# uController_Untilities.net
KiCad netlist of a schematic drawn in Altium Designer
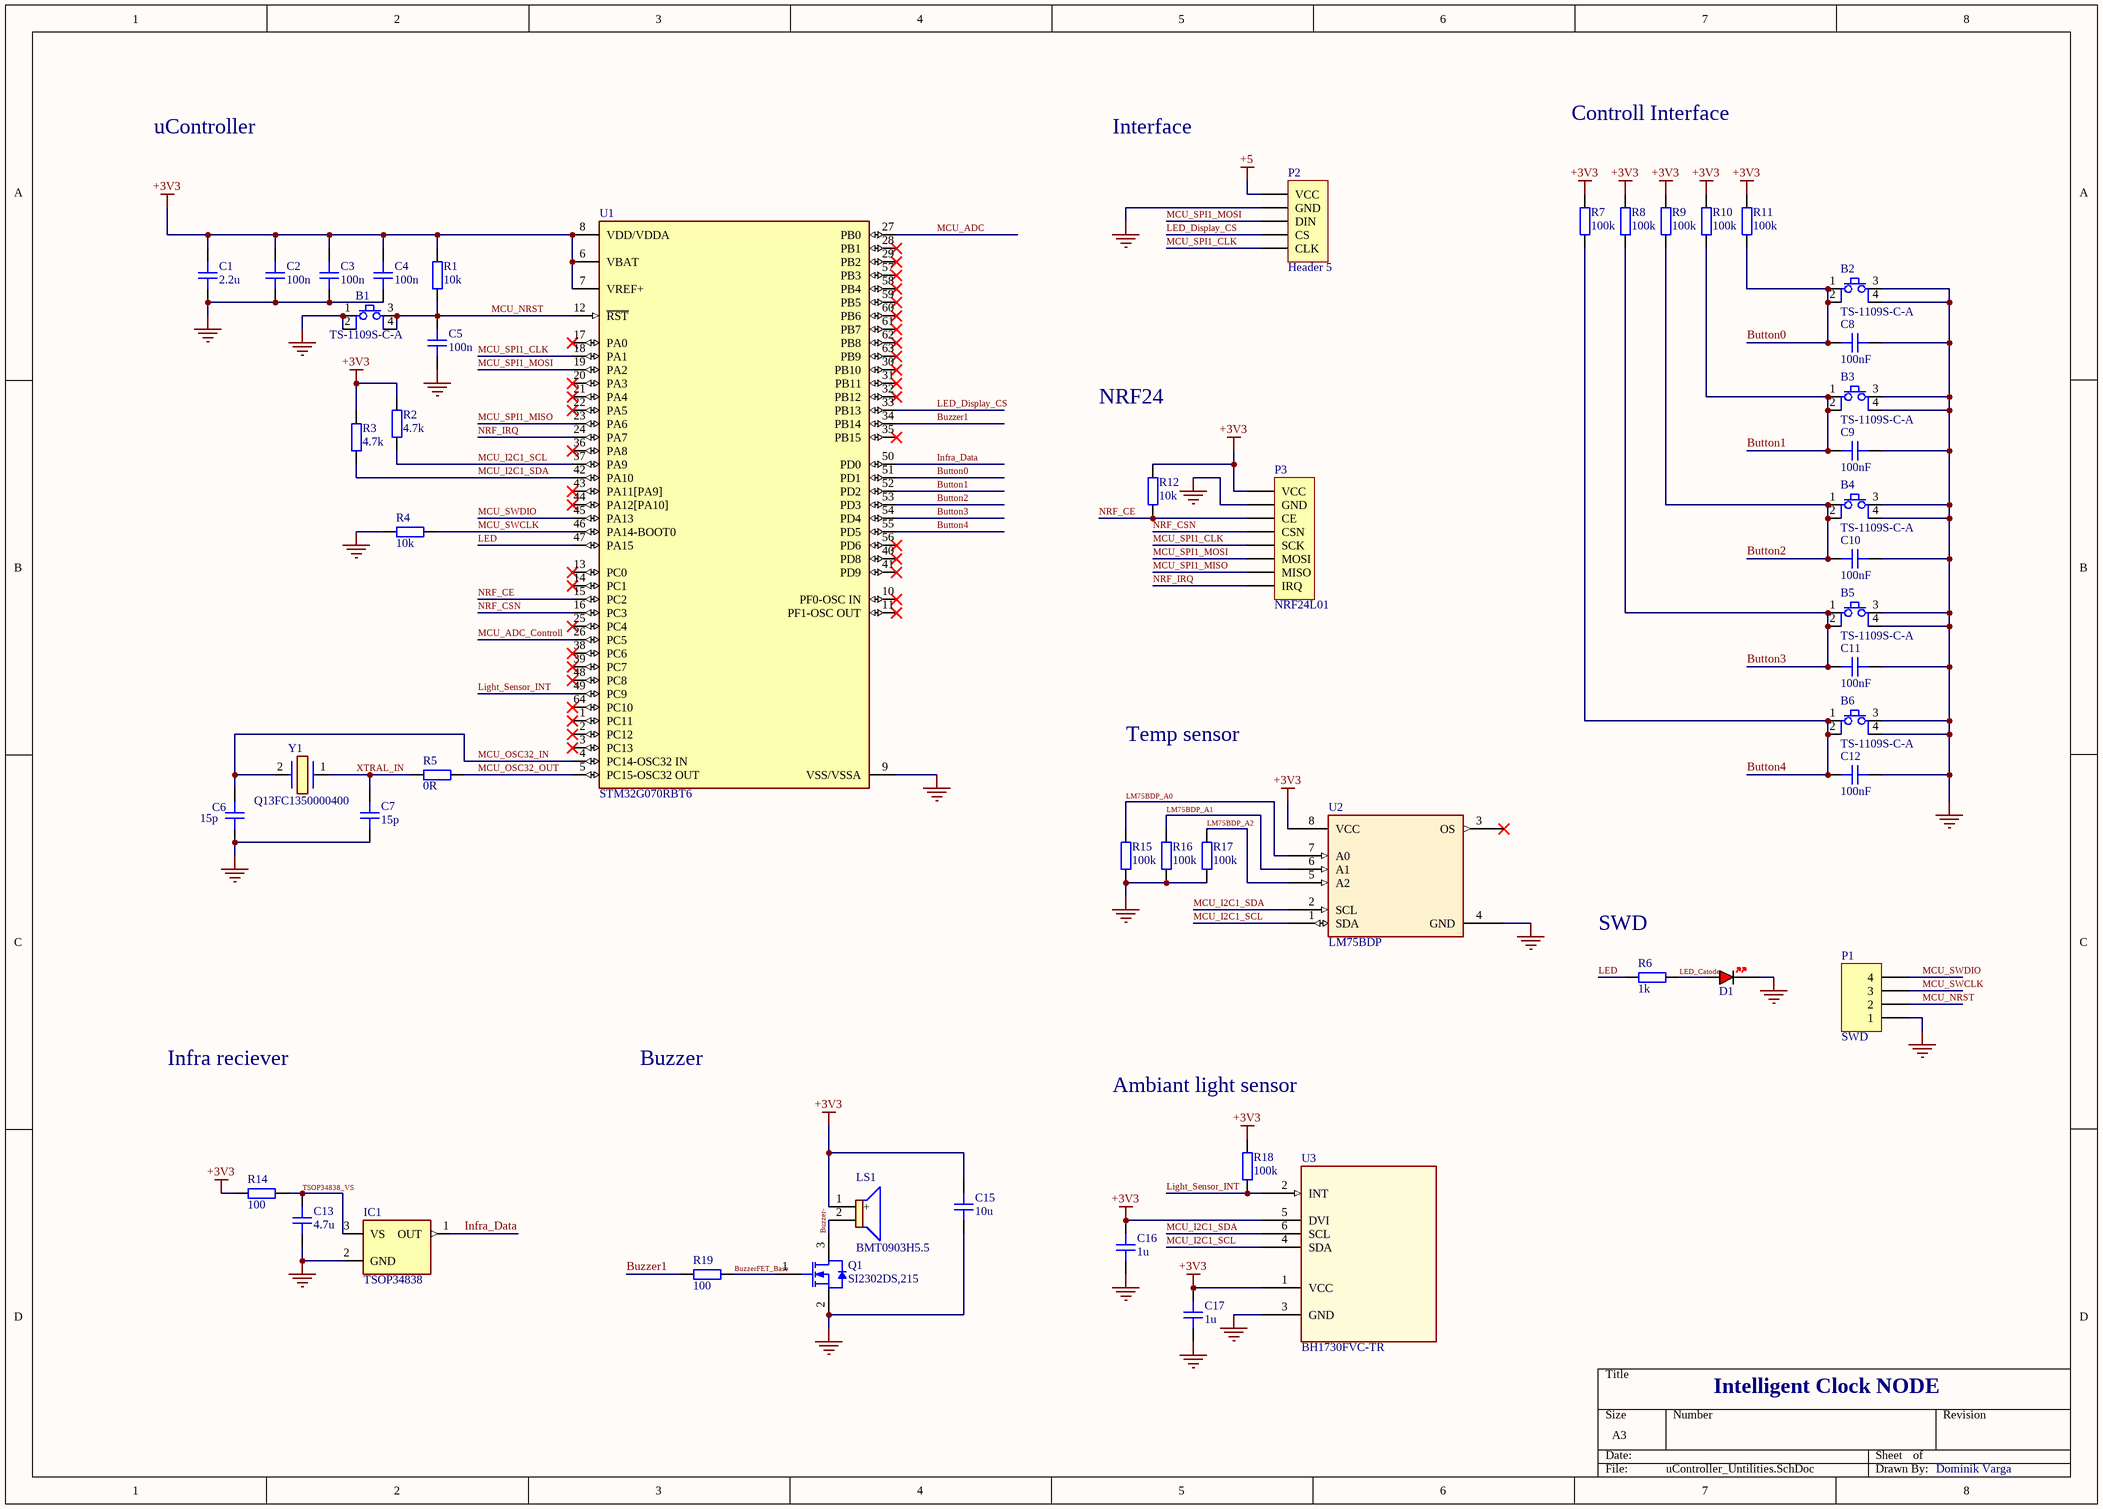
[diagram p0: uController_Untilities.SchDoc]

(export (version "E")
  (design (tool "Eeschema 10.0.6"))
  (components
    (comp (ref "B1")
      (value "TS-1109S-C-A")
      (footprint "SMD_Button")
      (description "Basic SMD button")
      (fields (field (name "MANUFACTURER") "XKB Connectivity"))
      (libsource (lib "OnlabComponents") (part "TS-1109S-C-A"))
    )
    (comp (ref "B2")
      (value "TS-1109S-C-A")
      (footprint "SMD_Button")
      (description "Basic SMD button")
      (fields (field (name "MANUFACTURER") "XKB Connectivity"))
      (libsource (lib "OnlabComponents") (part "TS-1109S-C-A"))
    )
    (comp (ref "B3")
      (value "TS-1109S-C-A")
      (footprint "SMD_Button")
      (description "Basic SMD button")
      (fields (field (name "MANUFACTURER") "XKB Connectivity"))
      (libsource (lib "OnlabComponents") (part "TS-1109S-C-A"))
    )
    (comp (ref "B4")
      (value "TS-1109S-C-A")
      (footprint "SMD_Button")
      (description "Basic SMD button")
      (fields (field (name "MANUFACTURER") "XKB Connectivity"))
      (libsource (lib "OnlabComponents") (part "TS-1109S-C-A"))
    )
    (comp (ref "B5")
      (value "TS-1109S-C-A")
      (footprint "SMD_Button")
      (description "Basic SMD button")
      (fields (field (name "MANUFACTURER") "XKB Connectivity"))
      (libsource (lib "OnlabComponents") (part "TS-1109S-C-A"))
    )
    (comp (ref "B6")
      (value "TS-1109S-C-A")
      (footprint "SMD_Button")
      (description "Basic SMD button")
      (fields (field (name "MANUFACTURER") "XKB Connectivity"))
      (libsource (lib "OnlabComponents") (part "TS-1109S-C-A"))
    )
    (comp (ref "C1")
      (value "2.2u")
      (footprint "CAP_0603")
      (description "Capacitor SMD 0603 10V")
      (libsource (lib "Schematic-Lib-PhilsLab") (part "CAP_0603_10V"))
    )
    (comp (ref "C2")
      (value "100n")
      (footprint "CAP_0603")
      (description "Capacitor SMD 0603 10V")
      (libsource (lib "Schematic-Lib-PhilsLab") (part "CAP_0603_10V"))
    )
    (comp (ref "C3")
      (value "100n")
      (footprint "CAP_0603")
      (description "Capacitor SMD 0603 10V")
      (libsource (lib "Schematic-Lib-PhilsLab") (part "CAP_0603_10V"))
    )
    (comp (ref "C4")
      (value "100n")
      (footprint "CAP_0603")
      (description "Capacitor SMD 0603 10V")
      (libsource (lib "Schematic-Lib-PhilsLab") (part "CAP_0603_10V"))
    )
    (comp (ref "C5")
      (value "100n")
      (footprint "CAP_0603")
      (description "Capacitor SMD 0603 10V")
      (libsource (lib "Schematic-Lib-PhilsLab") (part "CAP_0603_10V"))
    )
    (comp (ref "C6")
      (value "15p")
      (footprint "CAP_0603")
      (description "Capacitor SMD 0603 10V")
      (libsource (lib "Schematic-Lib-PhilsLab") (part "CAP_0603_10V"))
    )
    (comp (ref "C7")
      (value "15p")
      (footprint "CAP_0603")
      (description "Capacitor SMD 0603 10V")
      (libsource (lib "Schematic-Lib-PhilsLab") (part "CAP_0603_10V"))
    )
    (comp (ref "C8")
      (value "100nF")
      (footprint "CAP_0603")
      (description "Capacitor SMD 0603 10V")
      (libsource (lib "Schematic-Lib-PhilsLab") (part "CAP_0603_10V"))
    )
    (comp (ref "C9")
      (value "100nF")
      (footprint "CAP_0603")
      (description "Capacitor SMD 0603 10V")
      (libsource (lib "Schematic-Lib-PhilsLab") (part "CAP_0603_10V"))
    )
    (comp (ref "C10")
      (value "100nF")
      (footprint "CAP_0603")
      (description "Capacitor SMD 0603 10V")
      (libsource (lib "Schematic-Lib-PhilsLab") (part "CAP_0603_10V"))
    )
    (comp (ref "C11")
      (value "100nF")
      (footprint "CAP_0603")
      (description "Capacitor SMD 0603 10V")
      (libsource (lib "Schematic-Lib-PhilsLab") (part "CAP_0603_10V"))
    )
    (comp (ref "C12")
      (value "100nF")
      (footprint "CAP_0603")
      (description "Capacitor SMD 0603 10V")
      (libsource (lib "Schematic-Lib-PhilsLab") (part "CAP_0603_10V"))
    )
    (comp (ref "C13")
      (value "4.7u")
      (footprint "CAP_0603")
      (description "Capacitor SMD 0603 10V")
      (libsource (lib "Schematic-Lib-PhilsLab") (part "CAP_0603_10V"))
    )
    (comp (ref "C15")
      (value "10u")
      (footprint "CAP_0603")
      (description "Capacitor SMD 0603 10V")
      (libsource (lib "Schematic-Lib-PhilsLab") (part "CAP_0603_10V"))
    )
    (comp (ref "C16")
      (value "1u")
      (footprint "CAP_0603")
      (description "Capacitor SMD 0603 10V")
      (libsource (lib "Schematic-Lib-PhilsLab") (part "CAP_0603_10V"))
    )
    (comp (ref "C17")
      (value "1u")
      (footprint "CAP_0603")
      (description "Capacitor SMD 0603 10V")
      (libsource (lib "Schematic-Lib-PhilsLab") (part "CAP_0603_10V"))
    )
    (comp (ref "D1")
      (value "RED")
      (footprint "LED_0603_RED")
      (description "LED 0603 RED SMD")
      (libsource (lib "Schematic-Lib-PhilsLab") (part "LED_0603_RED"))
    )
    (comp (ref "IC1")
      (value "TSOP34838")
      (footprint "TSOP4856")
      (description "Integrated Circuit")
      (fields (field (name "MOUSER PART NUMBER") "782-TSOP34838"))
      (libsource (lib "OnlabComponents") (part "TSOP34838"))
    )
    (comp (ref "LS1")
      (value "BMT0903H5.5")
      (footprint "BMT0903H5.5")
      (description "Loudspeaker or Buzzer")
      (fields (field (name "MANUFACTURER") "BESTAR,LOUDITY"))
      (libsource (lib "OnlabComponents") (part "BMT0903H5.5"))
    )
    (comp (ref "P1")
      (value "SWD")
      (footprint "HDR1X4")
      (description "Header, 4-Pin")
      (fields (field (name "PUBLISHER") "Altium Limited"))
      (libsource (lib "Miscellaneous Connectors") (part "Header 4"))
    )
    (comp (ref "P2")
      (value "Header 5")
      (footprint "HDR1X5")
      (description "Header, 5-Pin")
      (fields (field (name "PUBLISHER") "Altium Limited"))
      (libsource (lib "Miscellaneous Connectors") (part "Header 5"))
    )
    (comp (ref "P3")
      (value "NRF24L01")
      (footprint "MHDR1X8")
      (description "Header, 8-Pin")
      (fields (field (name "PUBLISHER") "Altium Limited"))
      (libsource (lib "Miscellaneous Connectors") (part "MHDR1X8"))
    )
    (comp (ref "Q1")
      (value "SI2302DS,215")
      (footprint "NXP-SOT23_N")
      (description "N-Channel Enhancement Mode Field-Effect Transistor, 20 V, 2.5 A, 3-Pin SOT23, Tape and Reel")
      (fields (field (name "MANUFACTURER") "NXP Semiconductors"))
      (libsource (lib "Altium Content Vault") (part "NXP-NMOS-GSD-3_B"))
    )
    (comp (ref "R1")
      (value "10k")
      (footprint "RES_0603")
      (description "Resistor SMD 0603")
      (libsource (lib "Schematic-Lib-PhilsLab") (part "RES_0603"))
    )
    (comp (ref "R2")
      (value "4.7k")
      (footprint "RES_0603")
      (description "Resistor SMD 0603")
      (libsource (lib "Schematic-Lib-PhilsLab") (part "RES_0603"))
    )
    (comp (ref "R3")
      (value "4.7k")
      (footprint "RES_0603")
      (description "Resistor SMD 0603")
      (libsource (lib "Schematic-Lib-PhilsLab") (part "RES_0603"))
    )
    (comp (ref "R4")
      (value "10k")
      (footprint "RES_0603")
      (description "Resistor SMD 0603")
      (libsource (lib "Schematic-Lib-PhilsLab") (part "RES_0603"))
    )
    (comp (ref "R5")
      (value "0R")
      (footprint "RES_0603")
      (description "Resistor SMD 0603")
      (libsource (lib "Schematic-Lib-PhilsLab") (part "RES_0603"))
    )
    (comp (ref "R6")
      (value "1k")
      (footprint "RES_0603")
      (description "Resistor SMD 0603")
      (libsource (lib "Schematic-Lib-PhilsLab") (part "RES_0603"))
    )
    (comp (ref "R7")
      (value "100k")
      (footprint "RES_0603")
      (description "Resistor SMD 0603")
      (libsource (lib "Schematic-Lib-PhilsLab") (part "RES_0603"))
    )
    (comp (ref "R8")
      (value "100k")
      (footprint "RES_0603")
      (description "Resistor SMD 0603")
      (libsource (lib "Schematic-Lib-PhilsLab") (part "RES_0603"))
    )
    (comp (ref "R9")
      (value "100k")
      (footprint "RES_0603")
      (description "Resistor SMD 0603")
      (libsource (lib "Schematic-Lib-PhilsLab") (part "RES_0603"))
    )
    (comp (ref "R10")
      (value "100k")
      (footprint "RES_0603")
      (description "Resistor SMD 0603")
      (libsource (lib "Schematic-Lib-PhilsLab") (part "RES_0603"))
    )
    (comp (ref "R11")
      (value "100k")
      (footprint "RES_0603")
      (description "Resistor SMD 0603")
      (libsource (lib "Schematic-Lib-PhilsLab") (part "RES_0603"))
    )
    (comp (ref "R12")
      (value "10k")
      (footprint "RES_0603")
      (description "Resistor SMD 0603")
      (libsource (lib "Schematic-Lib-PhilsLab") (part "RES_0603"))
    )
    (comp (ref "R14")
      (value "100")
      (footprint "RES_0603")
      (description "Resistor SMD 0603")
      (libsource (lib "Schematic-Lib-PhilsLab") (part "RES_0603"))
    )
    (comp (ref "R15")
      (value "100k")
      (footprint "RES_0603")
      (description "Resistor SMD 0603")
      (libsource (lib "Schematic-Lib-PhilsLab") (part "RES_0603"))
    )
    (comp (ref "R16")
      (value "100k")
      (footprint "RES_0603")
      (description "Resistor SMD 0603")
      (libsource (lib "Schematic-Lib-PhilsLab") (part "RES_0603"))
    )
    (comp (ref "R17")
      (value "100k")
      (footprint "RES_0603")
      (description "Resistor SMD 0603")
      (libsource (lib "Schematic-Lib-PhilsLab") (part "RES_0603"))
    )
    (comp (ref "R18")
      (value "100k")
      (footprint "RES_0603")
      (description "Resistor SMD 0603")
      (libsource (lib "Schematic-Lib-PhilsLab") (part "RES_0603"))
    )
    (comp (ref "R19")
      (value "100")
      (footprint "RES_0603")
      (description "Resistor SMD 0603")
      (libsource (lib "Schematic-Lib-PhilsLab") (part "RES_0603"))
    )
    (comp (ref "U1")
      (value "STM32G070RBT6")
      (footprint "FP-LQFP64-5W-MFG")
      (description "IC MCU 32BIT 128KB FLASH 64LQFP")
      (libsource (lib "Altium Content Vault") (part "a2e03f705dc436ee8296d2452b1f2ed"))
    )
    (comp (ref "U2")
      (value "LM75BDP")
      (footprint "TSSOP8_3P1X3P1_NXP-M")
      (description "No Description Available")
      (fields (field (name "COPYRIGHT") "Copyright (C) 2022 Ultra Librarian. All rights reserved."))
      (libsource (lib "OnlabComponents") (part "LM75BDP"))
    )
    (comp (ref "U3")
      (value "BH1730FVC-TR")
      (footprint "SON_30FVC-TR_ROM-M")
      (description "Ambiant Light Sensor")
      (fields (field (name "COPYRIGHT") "Copyright (C) 2022 Ultra Librarian. All rights reserved."))
      (libsource (lib "OnlabComponents") (part "BH1730FVC-TR"))
    )
    (comp (ref "Y1")
      (value "Q13FC1350000400")
      (footprint "Q13FC1350000400")
      (description "Crystal or Oscillator")
      (libsource (lib "OnlabComponents") (part "Q13FC1350000400"))
    )
  )
  (nets
    (net (code "1") (name "+3V3") (class "Default")
      (node (ref "C1") (pin "2") (pinfunction "2_2") (pintype "passive"))
      (node (ref "C15") (pin "1") (pinfunction "1_1") (pintype "passive"))
      (node (ref "C16") (pin "2") (pinfunction "2_2") (pintype "passive"))
      (node (ref "C17") (pin "2") (pinfunction "2_2") (pintype "passive"))
      (node (ref "C2") (pin "2") (pinfunction "2_2") (pintype "passive"))
      (node (ref "C3") (pin "2") (pinfunction "2_2") (pintype "passive"))
      (node (ref "C4") (pin "2") (pinfunction "2_2") (pintype "passive"))
      (node (ref "LS1") (pin "1") (pinfunction "+_1") (pintype "passive"))
      (node (ref "P3") (pin "1") (pinfunction "VCC_1") (pintype "passive"))
      (node (ref "R1") (pin "2") (pinfunction "2_2") (pintype "passive"))
      (node (ref "R10") (pin "2") (pinfunction "2_2") (pintype "passive"))
      (node (ref "R11") (pin "2") (pinfunction "2_2") (pintype "passive"))
      (node (ref "R12") (pin "1") (pinfunction "1_1") (pintype "passive"))
      (node (ref "R14") (pin "1") (pinfunction "1_1") (pintype "passive"))
      (node (ref "R18") (pin "1") (pinfunction "1_1") (pintype "passive"))
      (node (ref "R2") (pin "1") (pinfunction "1_1") (pintype "passive"))
      (node (ref "R3") (pin "1") (pinfunction "1_1") (pintype "passive"))
      (node (ref "R7") (pin "2") (pinfunction "2_2") (pintype "passive"))
      (node (ref "R8") (pin "2") (pinfunction "2_2") (pintype "passive"))
      (node (ref "R9") (pin "2") (pinfunction "2_2") (pintype "passive"))
      (node (ref "U1") (pin "6") (pinfunction "VBAT_6") (pintype "power_in"))
      (node (ref "U1") (pin "7") (pinfunction "VREF+_7") (pintype "passive"))
      (node (ref "U1") (pin "8") (pinfunction "VDD/VDDA_8") (pintype "power_in"))
      (node (ref "U2") (pin "8") (pinfunction "VCC_8") (pintype "power_in"))
      (node (ref "U3") (pin "1") (pinfunction "VCC_1") (pintype "power_in"))
      (node (ref "U3") (pin "5") (pinfunction "DVI_5") (pintype "passive"))
    )
    (net (code "2") (name "+5") (class "Default")
      (node (ref "P2") (pin "1") (pinfunction "VCC_1") (pintype "passive"))
    )
    (net (code "3") (name "/Button0") (class "Default")
      (node (ref "B2") (pin "1") (pinfunction "1_1") (pintype "passive"))
      (node (ref "B2") (pin "2") (pinfunction "2_2") (pintype "passive"))
      (node (ref "C8") (pin "1") (pinfunction "1_1") (pintype "passive"))
      (node (ref "R11") (pin "1") (pinfunction "1_1") (pintype "passive"))
      (node (ref "U1") (pin "51") (pinfunction "PD1_51") (pintype "bidirectional"))
    )
    (net (code "4") (name "/Button1") (class "Default")
      (node (ref "B3") (pin "1") (pinfunction "1_1") (pintype "passive"))
      (node (ref "B3") (pin "2") (pinfunction "2_2") (pintype "passive"))
      (node (ref "C9") (pin "1") (pinfunction "1_1") (pintype "passive"))
      (node (ref "R10") (pin "1") (pinfunction "1_1") (pintype "passive"))
      (node (ref "U1") (pin "52") (pinfunction "PD2_52") (pintype "bidirectional"))
    )
    (net (code "5") (name "/Button2") (class "Default")
      (node (ref "B4") (pin "1") (pinfunction "1_1") (pintype "passive"))
      (node (ref "B4") (pin "2") (pinfunction "2_2") (pintype "passive"))
      (node (ref "C10") (pin "1") (pinfunction "1_1") (pintype "passive"))
      (node (ref "R9") (pin "1") (pinfunction "1_1") (pintype "passive"))
      (node (ref "U1") (pin "53") (pinfunction "PD3_53") (pintype "bidirectional"))
    )
    (net (code "6") (name "/Button3") (class "Default")
      (node (ref "B5") (pin "1") (pinfunction "1_1") (pintype "passive"))
      (node (ref "B5") (pin "2") (pinfunction "2_2") (pintype "passive"))
      (node (ref "C11") (pin "1") (pinfunction "1_1") (pintype "passive"))
      (node (ref "R8") (pin "1") (pinfunction "1_1") (pintype "passive"))
      (node (ref "U1") (pin "54") (pinfunction "PD4_54") (pintype "bidirectional"))
    )
    (net (code "7") (name "/Button4") (class "Default")
      (node (ref "B6") (pin "1") (pinfunction "1_1") (pintype "passive"))
      (node (ref "B6") (pin "2") (pinfunction "2_2") (pintype "passive"))
      (node (ref "C12") (pin "1") (pinfunction "1_1") (pintype "passive"))
      (node (ref "R7") (pin "1") (pinfunction "1_1") (pintype "passive"))
      (node (ref "U1") (pin "55") (pinfunction "PD5_55") (pintype "bidirectional"))
    )
    (net (code "8") (name "/Buzzer-") (class "Default")
      (node (ref "LS1") (pin "2") (pintype "passive"))
      (node (ref "Q1") (pin "3") (pinfunction "D_3") (pintype "passive"))
    )
    (net (code "9") (name "/Buzzer1") (class "Default")
      (node (ref "R19") (pin "1") (pinfunction "1_1") (pintype "passive"))
      (node (ref "U1") (pin "34") (pinfunction "PB14_34") (pintype "bidirectional"))
    )
    (net (code "10") (name "/BuzzerFET_Base") (class "Default")
      (node (ref "Q1") (pin "1") (pinfunction "G_1") (pintype "passive"))
      (node (ref "R19") (pin "2") (pinfunction "2_2") (pintype "passive"))
    )
    (net (code "11") (name "/Infra_Data") (class "Default")
      (node (ref "IC1") (pin "1") (pinfunction "OUT_1") (pintype "output"))
      (node (ref "U1") (pin "50") (pinfunction "PD0_50") (pintype "bidirectional"))
    )
    (net (code "12") (name "/LED") (class "Default")
      (node (ref "R6") (pin "2") (pinfunction "2_2") (pintype "passive"))
      (node (ref "U1") (pin "47") (pinfunction "PA15_47") (pintype "bidirectional"))
    )
    (net (code "13") (name "/LED_Catode") (class "Default")
      (node (ref "D1") (pin "A") (pinfunction "A_A") (pintype "passive"))
      (node (ref "R6") (pin "1") (pinfunction "1_1") (pintype "passive"))
    )
    (net (code "14") (name "/LED_Display_CS") (class "Default")
      (node (ref "P2") (pin "4") (pinfunction "CS_4") (pintype "passive"))
      (node (ref "U1") (pin "33") (pinfunction "PB13_33") (pintype "bidirectional"))
    )
    (net (code "15") (name "/LM75BDP_A0") (class "Default")
      (node (ref "R15") (pin "1") (pinfunction "1_1") (pintype "passive"))
      (node (ref "U2") (pin "7") (pinfunction "A0_7") (pintype "input"))
    )
    (net (code "16") (name "/LM75BDP_A1") (class "Default")
      (node (ref "R16") (pin "1") (pinfunction "1_1") (pintype "passive"))
      (node (ref "U2") (pin "6") (pinfunction "A1_6") (pintype "input"))
    )
    (net (code "17") (name "/LM75BDP_A2") (class "Default")
      (node (ref "R17") (pin "1") (pinfunction "1_1") (pintype "passive"))
      (node (ref "U2") (pin "5") (pinfunction "A2_5") (pintype "input"))
    )
    (net (code "18") (name "/Light_Sensor_INT") (class "Default")
      (node (ref "R18") (pin "2") (pinfunction "2_2") (pintype "passive"))
      (node (ref "U1") (pin "49") (pinfunction "PC9_49") (pintype "bidirectional"))
      (node (ref "U3") (pin "2") (pinfunction "INT_2") (pintype "input"))
    )
    (net (code "19") (name "/MCU_ADC") (class "Default")
      (node (ref "U1") (pin "27") (pinfunction "PB0_27") (pintype "bidirectional"))
    )
    (net (code "20") (name "/MCU_ADC_Controll") (class "Default")
      (node (ref "U1") (pin "26") (pinfunction "PC5_26") (pintype "bidirectional"))
    )
    (net (code "21") (name "/MCU_I2C1_SCL") (class "Default")
      (node (ref "R2") (pin "2") (pinfunction "2_2") (pintype "passive"))
      (node (ref "U1") (pin "37") (pinfunction "PA9_37") (pintype "bidirectional"))
      (node (ref "U2") (pin "1") (pinfunction "SDA_1") (pintype "bidirectional"))
      (node (ref "U3") (pin "4") (pinfunction "SDA_4") (pintype "passive"))
    )
    (net (code "22") (name "/MCU_I2C1_SDA") (class "Default")
      (node (ref "R3") (pin "2") (pinfunction "2_2") (pintype "passive"))
      (node (ref "U1") (pin "42") (pinfunction "PA10_42") (pintype "bidirectional"))
      (node (ref "U2") (pin "2") (pinfunction "SCL_2") (pintype "input"))
      (node (ref "U3") (pin "6") (pinfunction "SCL_6") (pintype "passive"))
    )
    (net (code "23") (name "/MCU_NRST") (class "Default")
      (node (ref "B1") (pin "3") (pinfunction "3_3") (pintype "passive"))
      (node (ref "B1") (pin "4") (pinfunction "4_4") (pintype "passive"))
      (node (ref "C5") (pin "2") (pinfunction "2_2") (pintype "passive"))
      (node (ref "P1") (pin "2") (pinfunction "2_2") (pintype "passive"))
      (node (ref "R1") (pin "1") (pinfunction "1_1") (pintype "passive"))
      (node (ref "U1") (pin "12") (pinfunction "~{RST}_12") (pintype "input"))
    )
    (net (code "24") (name "/MCU_OSC32_IN") (class "Default")
      (node (ref "C6") (pin "2") (pinfunction "2_2") (pintype "passive"))
      (node (ref "U1") (pin "4") (pinfunction "PC14-OSC32_IN_4") (pintype "bidirectional"))
      (node (ref "Y1") (pin "2") (pinfunction "CRYSTAL_2_2") (pintype "passive"))
    )
    (net (code "25") (name "/MCU_OSC32_OUT") (class "Default")
      (node (ref "R5") (pin "1") (pinfunction "1_1") (pintype "passive"))
      (node (ref "U1") (pin "5") (pinfunction "PC15-OSC32_OUT_5") (pintype "bidirectional"))
    )
    (net (code "26") (name "/MCU_SPI1_CLK") (class "Default")
      (node (ref "P2") (pin "5") (pinfunction "CLK_5") (pintype "passive"))
      (node (ref "P3") (pin "5") (pinfunction "SCK_5") (pintype "passive"))
      (node (ref "U1") (pin "18") (pinfunction "PA1_18") (pintype "bidirectional"))
    )
    (net (code "27") (name "/MCU_SPI1_MISO") (class "Default")
      (node (ref "P3") (pin "7") (pinfunction "MISO_7") (pintype "passive"))
      (node (ref "U1") (pin "23") (pinfunction "PA6_23") (pintype "bidirectional"))
    )
    (net (code "28") (name "/MCU_SPI1_MOSI") (class "Default")
      (node (ref "P2") (pin "3") (pinfunction "DIN_3") (pintype "passive"))
      (node (ref "P3") (pin "6") (pinfunction "MOSI_6") (pintype "passive"))
      (node (ref "U1") (pin "19") (pinfunction "PA2_19") (pintype "bidirectional"))
    )
    (net (code "29") (name "/MCU_SWCLK") (class "Default")
      (node (ref "P1") (pin "3") (pinfunction "3_3") (pintype "passive"))
      (node (ref "R4") (pin "1") (pinfunction "1_1") (pintype "passive"))
      (node (ref "U1") (pin "46") (pinfunction "PA14-BOOT0_46") (pintype "bidirectional"))
    )
    (net (code "30") (name "/MCU_SWDIO") (class "Default")
      (node (ref "P1") (pin "4") (pinfunction "4_4") (pintype "passive"))
      (node (ref "U1") (pin "45") (pinfunction "PA13_45") (pintype "bidirectional"))
    )
    (net (code "31") (name "/NRF_CE") (class "Default")
      (node (ref "P3") (pin "3") (pinfunction "CE_3") (pintype "passive"))
      (node (ref "R12") (pin "2") (pinfunction "2_2") (pintype "passive"))
      (node (ref "U1") (pin "15") (pinfunction "PC2_15") (pintype "bidirectional"))
    )
    (net (code "32") (name "/NRF_CSN") (class "Default")
      (node (ref "P3") (pin "4") (pinfunction "CSN_4") (pintype "passive"))
      (node (ref "U1") (pin "16") (pinfunction "PC3_16") (pintype "bidirectional"))
    )
    (net (code "33") (name "/NRF_IRQ") (class "Default")
      (node (ref "P3") (pin "8") (pinfunction "IRQ_8") (pintype "passive"))
      (node (ref "U1") (pin "24") (pinfunction "PA7_24") (pintype "bidirectional"))
    )
    (net (code "34") (name "/TSOP34838_VS") (class "Default")
      (node (ref "C13") (pin "2") (pinfunction "2_2") (pintype "passive"))
      (node (ref "IC1") (pin "3") (pinfunction "VS_3") (pintype "power_in"))
      (node (ref "R14") (pin "2") (pinfunction "2_2") (pintype "passive"))
    )
    (net (code "35") (name "/XTRAL_IN") (class "Default")
      (node (ref "C7") (pin "2") (pinfunction "2_2") (pintype "passive"))
      (node (ref "R5") (pin "2") (pinfunction "2_2") (pintype "passive"))
      (node (ref "Y1") (pin "1") (pintype "passive"))
    )
    (net (code "36") (name "GND") (class "Default")
      (node (ref "B1") (pin "1") (pinfunction "1_1") (pintype "passive"))
      (node (ref "B1") (pin "2") (pinfunction "2_2") (pintype "passive"))
      (node (ref "B2") (pin "3") (pinfunction "3_3") (pintype "passive"))
      (node (ref "B2") (pin "4") (pinfunction "4_4") (pintype "passive"))
      (node (ref "B3") (pin "3") (pinfunction "3_3") (pintype "passive"))
      (node (ref "B3") (pin "4") (pinfunction "4_4") (pintype "passive"))
      (node (ref "B4") (pin "3") (pinfunction "3_3") (pintype "passive"))
      (node (ref "B4") (pin "4") (pinfunction "4_4") (pintype "passive"))
      (node (ref "B5") (pin "3") (pinfunction "3_3") (pintype "passive"))
      (node (ref "B5") (pin "4") (pinfunction "4_4") (pintype "passive"))
      (node (ref "B6") (pin "3") (pinfunction "3_3") (pintype "passive"))
      (node (ref "B6") (pin "4") (pinfunction "4_4") (pintype "passive"))
      (node (ref "C1") (pin "1") (pinfunction "1_1") (pintype "passive"))
      (node (ref "C10") (pin "2") (pinfunction "2_2") (pintype "passive"))
      (node (ref "C11") (pin "2") (pinfunction "2_2") (pintype "passive"))
      (node (ref "C12") (pin "2") (pinfunction "2_2") (pintype "passive"))
      (node (ref "C13") (pin "1") (pinfunction "1_1") (pintype "passive"))
      (node (ref "C15") (pin "2") (pinfunction "2_2") (pintype "passive"))
      (node (ref "C16") (pin "1") (pinfunction "1_1") (pintype "passive"))
      (node (ref "C17") (pin "1") (pinfunction "1_1") (pintype "passive"))
      (node (ref "C2") (pin "1") (pinfunction "1_1") (pintype "passive"))
      (node (ref "C3") (pin "1") (pinfunction "1_1") (pintype "passive"))
      (node (ref "C4") (pin "1") (pinfunction "1_1") (pintype "passive"))
      (node (ref "C5") (pin "1") (pinfunction "1_1") (pintype "passive"))
      (node (ref "C6") (pin "1") (pinfunction "1_1") (pintype "passive"))
      (node (ref "C7") (pin "1") (pinfunction "1_1") (pintype "passive"))
      (node (ref "C8") (pin "2") (pinfunction "2_2") (pintype "passive"))
      (node (ref "C9") (pin "2") (pinfunction "2_2") (pintype "passive"))
      (node (ref "D1") (pin "K") (pinfunction "K_K") (pintype "passive"))
      (node (ref "IC1") (pin "2") (pinfunction "GND_2") (pintype "power_in"))
      (node (ref "P1") (pin "1") (pinfunction "1_1") (pintype "passive"))
      (node (ref "P2") (pin "2") (pinfunction "GND_2") (pintype "passive"))
      (node (ref "P3") (pin "2") (pinfunction "GND_2") (pintype "passive"))
      (node (ref "Q1") (pin "2") (pinfunction "S_2") (pintype "passive"))
      (node (ref "R15") (pin "2") (pinfunction "2_2") (pintype "passive"))
      (node (ref "R16") (pin "2") (pinfunction "2_2") (pintype "passive"))
      (node (ref "R17") (pin "2") (pinfunction "2_2") (pintype "passive"))
      (node (ref "R4") (pin "2") (pinfunction "2_2") (pintype "passive"))
      (node (ref "U1") (pin "9") (pinfunction "VSS/VSSA_9") (pintype "power_in"))
      (node (ref "U2") (pin "4") (pinfunction "GND_4") (pintype "power_in"))
      (node (ref "U3") (pin "3") (pinfunction "GND_3") (pintype "passive"))
    )
    (net (code "37") (name "unconnected-(U1-PA0-Pad17)") (class "Default")
      (node (ref "U1") (pin "17") (pinfunction "PA0_17") (pintype "bidirectional+no_connect"))
    )
    (net (code "38") (name "unconnected-(U1-PA3-Pad20)") (class "Default")
      (node (ref "U1") (pin "20") (pinfunction "PA3_20") (pintype "bidirectional+no_connect"))
    )
    (net (code "39") (name "unconnected-(U1-PA4-Pad21)") (class "Default")
      (node (ref "U1") (pin "21") (pinfunction "PA4_21") (pintype "bidirectional+no_connect"))
    )
    (net (code "40") (name "unconnected-(U1-PA5-Pad22)") (class "Default")
      (node (ref "U1") (pin "22") (pinfunction "PA5_22") (pintype "bidirectional+no_connect"))
    )
    (net (code "41") (name "unconnected-(U1-PA8-Pad36)") (class "Default")
      (node (ref "U1") (pin "36") (pinfunction "PA8_36") (pintype "bidirectional+no_connect"))
    )
    (net (code "42") (name "unconnected-(U1-PA11[PA9]-Pad43)") (class "Default")
      (node (ref "U1") (pin "43") (pinfunction "PA11[PA9]_43") (pintype "bidirectional+no_connect"))
    )
    (net (code "43") (name "unconnected-(U1-PA12[PA10]-Pad44)") (class "Default")
      (node (ref "U1") (pin "44") (pinfunction "PA12[PA10]_44") (pintype "bidirectional+no_connect"))
    )
    (net (code "44") (name "unconnected-(U1-PB1-Pad28)") (class "Default")
      (node (ref "U1") (pin "28") (pinfunction "PB1_28") (pintype "bidirectional+no_connect"))
    )
    (net (code "45") (name "unconnected-(U1-PB2-Pad29)") (class "Default")
      (node (ref "U1") (pin "29") (pinfunction "PB2_29") (pintype "bidirectional+no_connect"))
    )
    (net (code "46") (name "unconnected-(U1-PB3-Pad57)") (class "Default")
      (node (ref "U1") (pin "57") (pinfunction "PB3_57") (pintype "bidirectional+no_connect"))
    )
    (net (code "47") (name "unconnected-(U1-PB4-Pad58)") (class "Default")
      (node (ref "U1") (pin "58") (pinfunction "PB4_58") (pintype "bidirectional+no_connect"))
    )
    (net (code "48") (name "unconnected-(U1-PB5-Pad59)") (class "Default")
      (node (ref "U1") (pin "59") (pinfunction "PB5_59") (pintype "bidirectional+no_connect"))
    )
    (net (code "49") (name "unconnected-(U1-PB6-Pad60)") (class "Default")
      (node (ref "U1") (pin "60") (pinfunction "PB6_60") (pintype "bidirectional+no_connect"))
    )
    (net (code "50") (name "unconnected-(U1-PB7-Pad61)") (class "Default")
      (node (ref "U1") (pin "61") (pinfunction "PB7_61") (pintype "bidirectional+no_connect"))
    )
    (net (code "51") (name "unconnected-(U1-PB8-Pad62)") (class "Default")
      (node (ref "U1") (pin "62") (pinfunction "PB8_62") (pintype "bidirectional+no_connect"))
    )
    (net (code "52") (name "unconnected-(U1-PB9-Pad63)") (class "Default")
      (node (ref "U1") (pin "63") (pinfunction "PB9_63") (pintype "bidirectional+no_connect"))
    )
    (net (code "53") (name "unconnected-(U1-PB10-Pad30)") (class "Default")
      (node (ref "U1") (pin "30") (pinfunction "PB10_30") (pintype "bidirectional+no_connect"))
    )
    (net (code "54") (name "unconnected-(U1-PB11-Pad31)") (class "Default")
      (node (ref "U1") (pin "31") (pinfunction "PB11_31") (pintype "bidirectional+no_connect"))
    )
    (net (code "55") (name "unconnected-(U1-PB12-Pad32)") (class "Default")
      (node (ref "U1") (pin "32") (pinfunction "PB12_32") (pintype "bidirectional+no_connect"))
    )
    (net (code "56") (name "unconnected-(U1-PB15-Pad35)") (class "Default")
      (node (ref "U1") (pin "35") (pinfunction "PB15_35") (pintype "bidirectional+no_connect"))
    )
    (net (code "57") (name "unconnected-(U1-PC0-Pad13)") (class "Default")
      (node (ref "U1") (pin "13") (pinfunction "PC0_13") (pintype "bidirectional+no_connect"))
    )
    (net (code "58") (name "unconnected-(U1-PC1-Pad14)") (class "Default")
      (node (ref "U1") (pin "14") (pinfunction "PC1_14") (pintype "bidirectional+no_connect"))
    )
    (net (code "59") (name "unconnected-(U1-PC4-Pad25)") (class "Default")
      (node (ref "U1") (pin "25") (pinfunction "PC4_25") (pintype "bidirectional+no_connect"))
    )
    (net (code "60") (name "unconnected-(U1-PC6-Pad38)") (class "Default")
      (node (ref "U1") (pin "38") (pinfunction "PC6_38") (pintype "bidirectional+no_connect"))
    )
    (net (code "61") (name "unconnected-(U1-PC7-Pad39)") (class "Default")
      (node (ref "U1") (pin "39") (pinfunction "PC7_39") (pintype "bidirectional+no_connect"))
    )
    (net (code "62") (name "unconnected-(U1-PC8-Pad48)") (class "Default")
      (node (ref "U1") (pin "48") (pinfunction "PC8_48") (pintype "bidirectional+no_connect"))
    )
    (net (code "63") (name "unconnected-(U1-PC10-Pad64)") (class "Default")
      (node (ref "U1") (pin "64") (pinfunction "PC10_64") (pintype "bidirectional+no_connect"))
    )
    (net (code "64") (name "unconnected-(U1-PC11-Pad1)") (class "Default")
      (node (ref "U1") (pin "1") (pinfunction "PC11_1") (pintype "bidirectional+no_connect"))
    )
    (net (code "65") (name "unconnected-(U1-PC12-Pad2)") (class "Default")
      (node (ref "U1") (pin "2") (pinfunction "PC12_2") (pintype "bidirectional+no_connect"))
    )
    (net (code "66") (name "unconnected-(U1-PC13-Pad3)") (class "Default")
      (node (ref "U1") (pin "3") (pinfunction "PC13_3") (pintype "bidirectional+no_connect"))
    )
    (net (code "67") (name "unconnected-(U1-PD6-Pad56)") (class "Default")
      (node (ref "U1") (pin "56") (pinfunction "PD6_56") (pintype "bidirectional+no_connect"))
    )
    (net (code "68") (name "unconnected-(U1-PD8-Pad40)") (class "Default")
      (node (ref "U1") (pin "40") (pinfunction "PD8_40") (pintype "bidirectional+no_connect"))
    )
    (net (code "69") (name "unconnected-(U1-PD9-Pad41)") (class "Default")
      (node (ref "U1") (pin "41") (pinfunction "PD9_41") (pintype "bidirectional+no_connect"))
    )
    (net (code "70") (name "unconnected-(U1-PF0-OSC_IN-Pad10)") (class "Default")
      (node (ref "U1") (pin "10") (pinfunction "PF0-OSC_IN_10") (pintype "bidirectional+no_connect"))
    )
    (net (code "71") (name "unconnected-(U1-PF1-OSC_OUT-Pad11)") (class "Default")
      (node (ref "U1") (pin "11") (pinfunction "PF1-OSC_OUT_11") (pintype "bidirectional+no_connect"))
    )
    (net (code "72") (name "unconnected-(U2-OS-Pad3)") (class "Default")
      (node (ref "U2") (pin "3") (pinfunction "OS_3") (pintype "output+no_connect"))
    )
  )
)
